# Pwr.net
KiCad netlist of a schematic drawn in Altium Designer
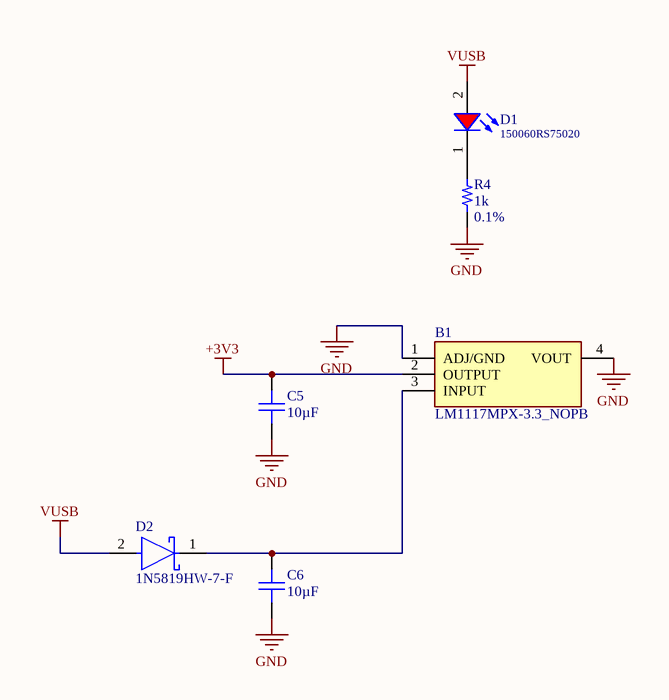
[diagram p0: Pwr.SchDoc]

(export (version "E")
  (design (tool "Eeschema 10.0.6"))
  (components
    (comp (ref "B1")
      (value "LM1117MPX-3.3_NOPB")
      (footprint "SOT230P700X180-4N")
      (description "Space saving 800-mA low-dropout linear regulator with internal current limit")
      (fields
        (field (name "MOUSER PART NUMBER") "926-LM1117MPX3.3NOPB")
        (field (name "MANUFACTURER_PART_NUMBER") "LM1117MPX-3.3/NOPB")
      )
      (libsource (lib "LM1117MPX-3.3_NOPB") (part "LM1117MPX-3.3_NOPB"))
    )
    (comp (ref "C5")
      (value "10µF")
      (footprint "FP-GRM188-0_2-IPC_B")
      (fields (field (name "Comment") "GRM188R61E106MA73J"))
      (libsource (lib "ILH") (part "Capacitor Voltage Rating"))
    )
    (comp (ref "C6")
      (value "10µF")
      (footprint "FP-GRM188-0_2-IPC_B")
      (fields (field (name "Comment") "GRM188R61E106MA73J"))
      (libsource (lib "ILH") (part "Capacitor Voltage Rating"))
    )
    (comp (ref "D1")
      (value "150060RS75020")
      (footprint "WL-SMCW_0603_H=0.25mm")
      (description "WL-SMCW SMT Mono-color Chip LED Waterclear, size 0603, Red, 2V, 140deg")
      (fields (field (name "PUBLISHER") "Wurth Elektronik"))
      (libsource (lib "ILH") (part "LED RED"))
    )
    (comp (ref "D2")
      (value "1N5819HW-7-F")
      (footprint "FP-SOD123-IPC_A")
      (description "DIODE SCHOTTKY 40V 1A SOD123")
      (libsource (lib "Altium Content Vault") (part "1d6ec82d83fb6aee721767c19dac4b9"))
    )
    (comp (ref "R4")
      (value "1k")
      (footprint "RESC1608X06L 0603 High Density")
      (description "SUSUMU - RG1608P-102-B-T5 - RES, THIN FILM, 1K, 0.1%, 0.1W, 0603")
      (fields (field (name "TOLERANCE") "0.1%") (field (name "Comment") "RG1608P-102-B-T5"))
      (libsource (lib "ILH") (part "Resistor Tolerance"))
    )
  )
  (nets
    (net (code "1") (name "+3V3") (class "Default")
      (node (ref "B1") (pin "2") (pinfunction "OUTPUT_2") (pintype "passive"))
      (node (ref "C5") (pin "2") (pinfunction "2_2") (pintype "passive"))
    )
    (net (code "2") (name "GND") (class "Default")
      (node (ref "B1") (pin "1") (pinfunction "ADJ/GND_1") (pintype "passive"))
      (node (ref "B1") (pin "4") (pinfunction "VOUT_4") (pintype "passive"))
      (node (ref "C5") (pin "1") (pinfunction "1_1") (pintype "passive"))
      (node (ref "C6") (pin "1") (pinfunction "1_1") (pintype "passive"))
      (node (ref "R4") (pin "1") (pinfunction "1_1") (pintype "passive"))
    )
    (net (code "3") (name "Net-(B1-INPUT)") (class "Default")
      (node (ref "B1") (pin "3") (pinfunction "INPUT_3") (pintype "passive"))
      (node (ref "C6") (pin "2") (pinfunction "2_2") (pintype "passive"))
      (node (ref "D2") (pin "1") (pinfunction "C_1") (pintype "passive"))
    )
    (net (code "4") (name "Net-(D1-K)") (class "Default")
      (node (ref "D1") (pin "1") (pinfunction "K_1") (pintype "passive"))
      (node (ref "R4") (pin "2") (pinfunction "2_2") (pintype "passive"))
    )
    (net (code "5") (name "VUSB") (class "Default")
      (node (ref "D1") (pin "2") (pinfunction "A_2") (pintype "passive"))
      (node (ref "D2") (pin "2") (pinfunction "A_2") (pintype "passive"))
    )
  )
)
